# ProPrj_FK407M3-VET6-V1_1-LCD-EB_2024-10-.net
KiCad netlist of a schematic drawn in EasyEDA Pro
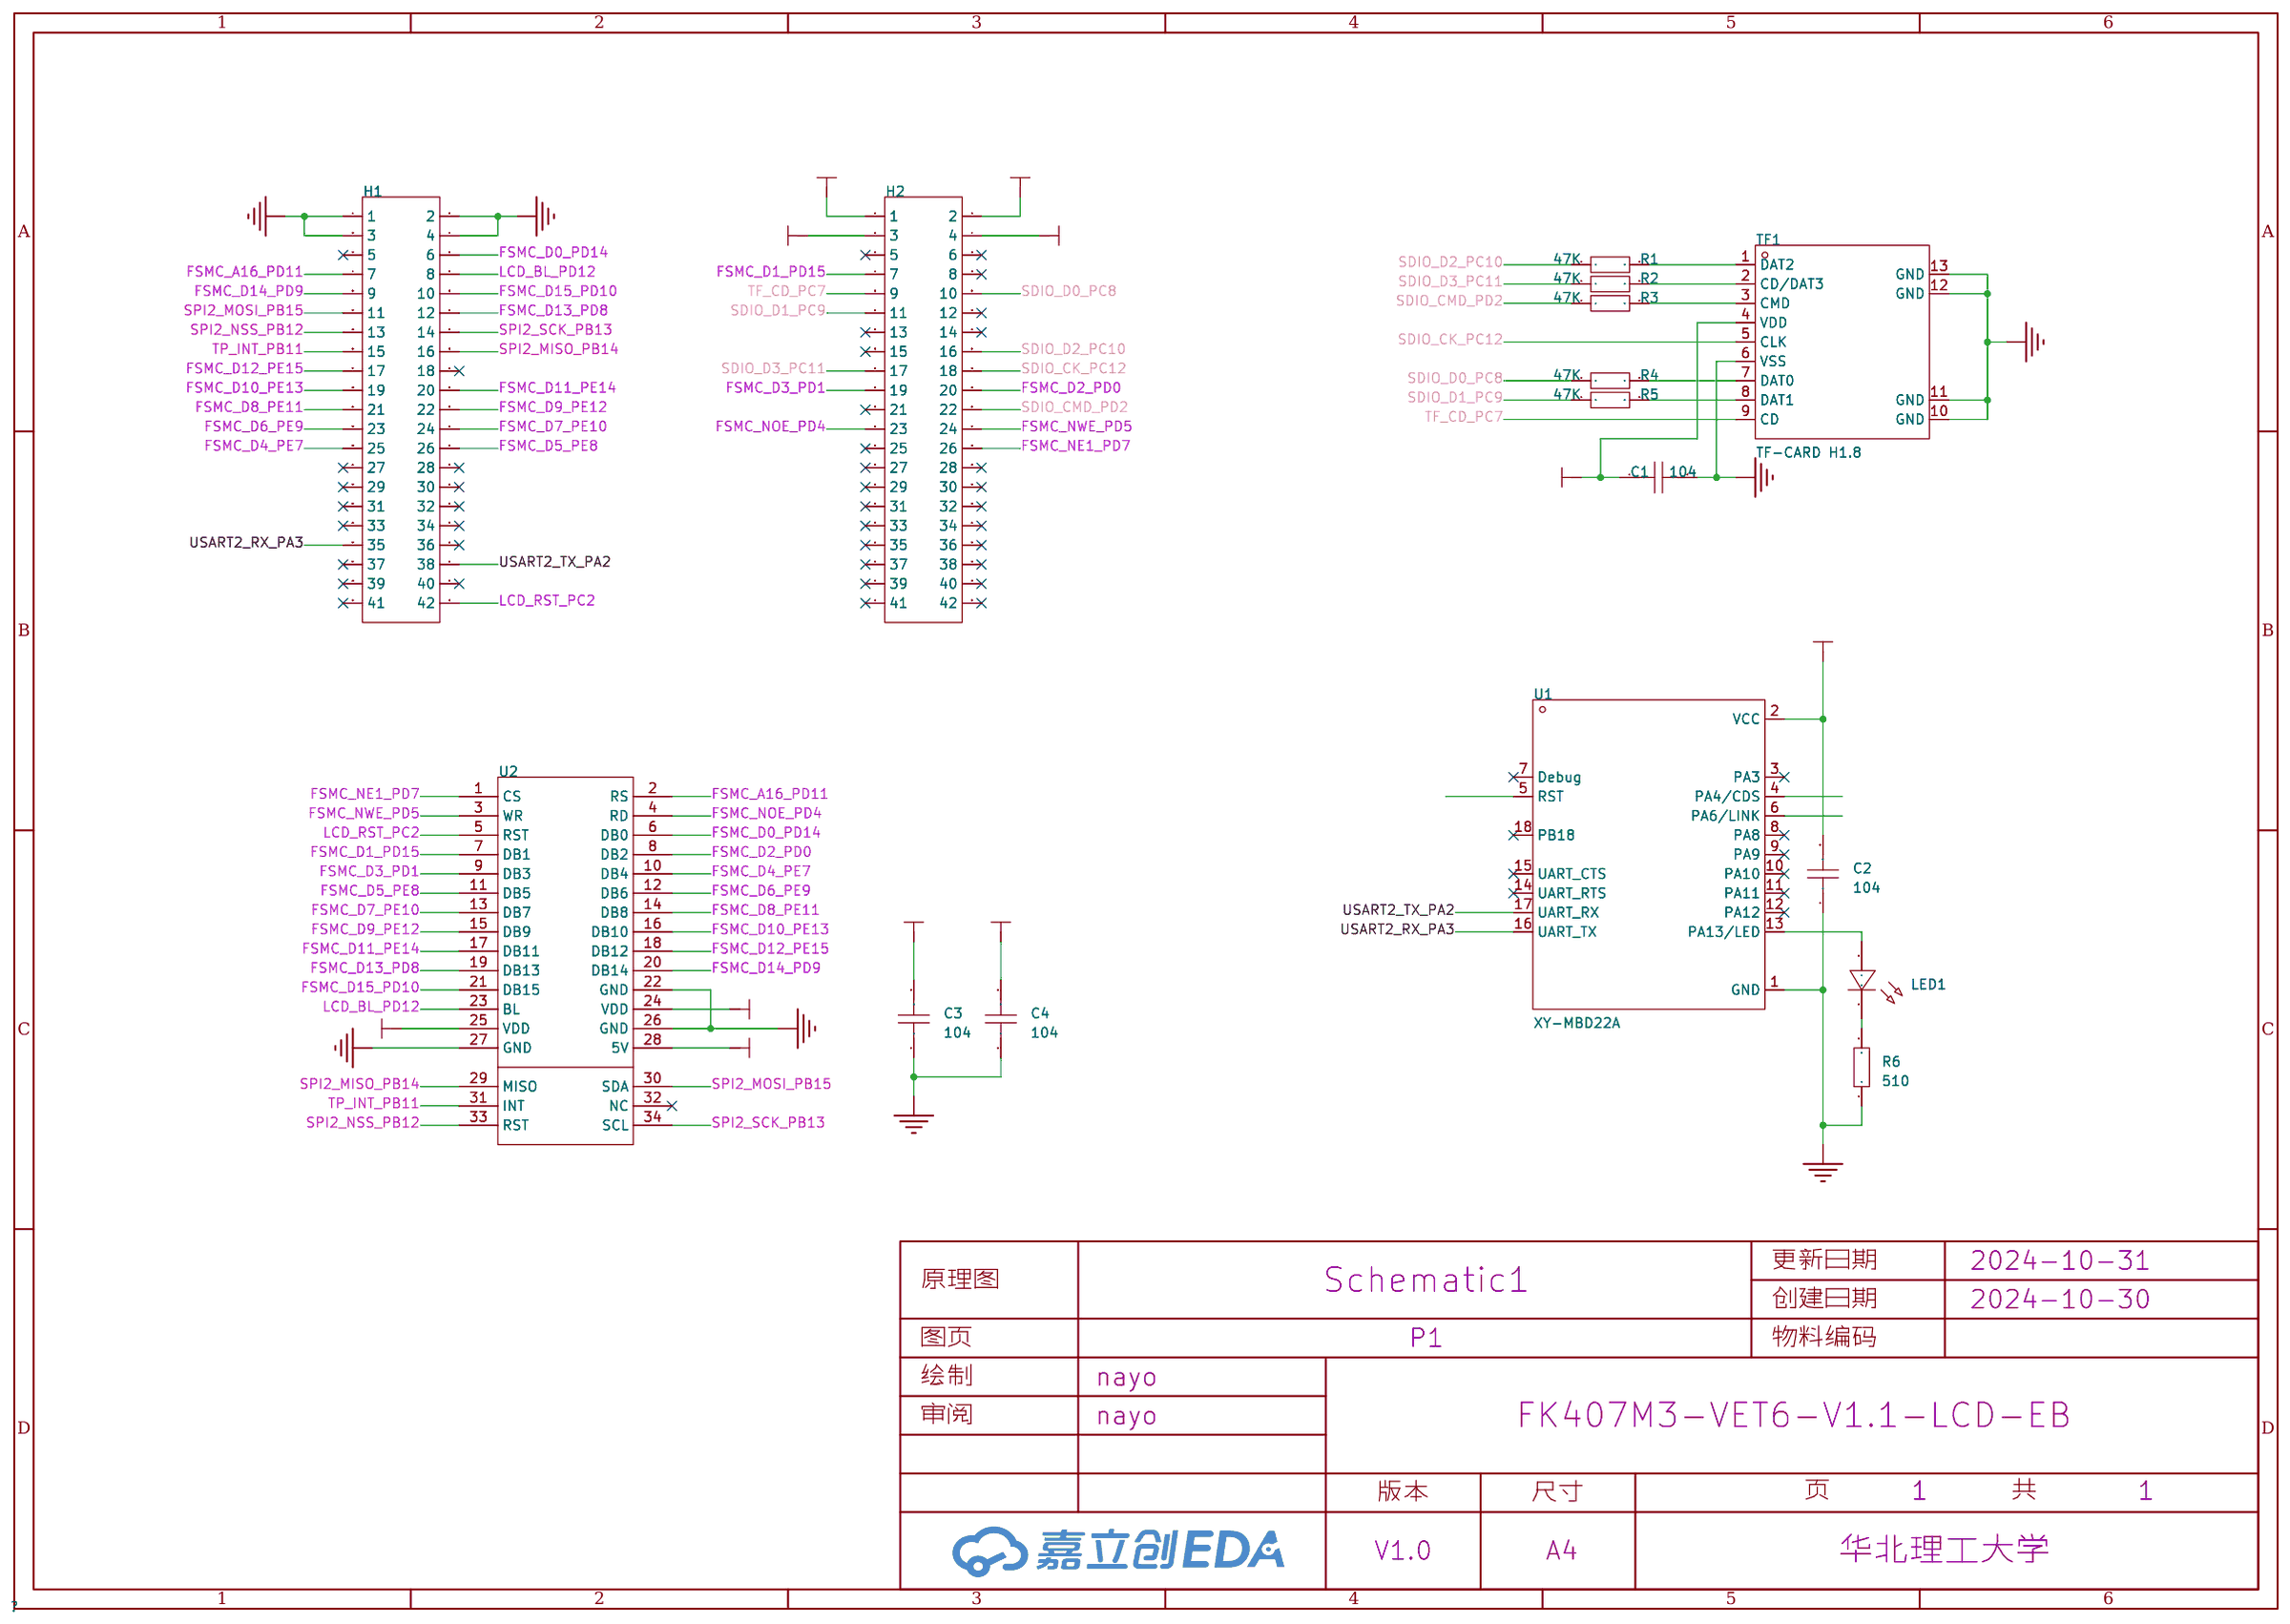
[diagram p0: schematic sheet]

(export (version "E")
  (design (tool "Eeschema 10.0.6"))
  (components
    (comp (ref "C1")
      (value "104")
      (footprint "easyedapro:C0603")
      (libsource (lib "easyedapro") (part "CapAcitance"))
    )
    (comp (ref "C2")
      (value "104")
      (footprint "easyedapro:C0603")
      (libsource (lib "easyedapro") (part "CapAcitance"))
    )
    (comp (ref "C3")
      (value "104")
      (footprint "easyedapro:C0603")
      (libsource (lib "easyedapro") (part "CapAcitance"))
    )
    (comp (ref "C4")
      (value "104")
      (footprint "easyedapro:C0603")
      (libsource (lib "easyedapro") (part "CapAcitance"))
    )
    (comp (ref "H1")
      (value "~")
      (footprint "easyedapro:HDR-F_2.54_2x21P")
      (libsource (lib "easyedapro") (part "HDR-F_2.54_2x21P"))
    )
    (comp (ref "H2")
      (value "~")
      (footprint "easyedapro:HDR-F_2.54_2x21P")
      (libsource (lib "easyedapro") (part "HDR-F_2.54_2x21P"))
    )
    (comp (ref "LED1")
      (value "~")
      (footprint "easyedapro:LED_0603")
      (libsource (lib "easyedapro") (part "LED_B"))
    )
    (comp (ref "R1") (value "47K") (footprint "easyedapro:R0603") (libsource (lib "easyedapro") (part "电阻")))
    (comp (ref "R2") (value "47K") (footprint "easyedapro:R0603") (libsource (lib "easyedapro") (part "电阻")))
    (comp (ref "R3") (value "47K") (footprint "easyedapro:R0603") (libsource (lib "easyedapro") (part "电阻")))
    (comp (ref "R4") (value "47K") (footprint "easyedapro:R0603") (libsource (lib "easyedapro") (part "电阻")))
    (comp (ref "R5") (value "47K") (footprint "easyedapro:R0603") (libsource (lib "easyedapro") (part "电阻")))
    (comp (ref "R6") (value "510") (footprint "easyedapro:R0603") (libsource (lib "easyedapro") (part "电阻")))
    (comp (ref "TF1")
      (value "TF-CARD H1.8")
      (footprint "easyedapro:TF-SMD_TF-CARD-H1.8")
      (description "卡连接方式:自弹式;卡类型:MicroSD卡(TF卡);连接器类型:卡座;本体最大高度:1.8mm;触头材质:铜合金;触头镀层:金;工作温度范围:-40°C~+70°C;")
      (fields (field (name "Manufacturer") "SHOU HAN(首韩)"))
      (libsource (lib "easyedapro") (part "TF-CARD H1.8"))
    )
    (comp (ref "U1")
      (value "XY-MBD22A")
      (footprint "easyedapro:wirelm-smd_xy-mbd22a")
      (libsource (lib "easyedapro") (part "XY-MBD22A"))
    )
    (comp (ref "U2")
      (value "~")
      (footprint "easyedapro:耀元鸿3.5寸TFT液晶显示屏并口串口电阻屏5点电容屏GT911彩屏LCD")
      (libsource (lib "easyedapro") (part "耀元鸿3.5寸TFT液晶显示屏并口串口电阻屏5点电容屏GT911彩屏LCD"))
    )
  )
  (nets
    (net (code "1") (name "/FSMC_A16_PD11") (class "Default")
      (node (ref "H1") (pin "7") (pinfunction "7_7") (pintype "input"))
      (node (ref "U2") (pin "2") (pinfunction "RS_2") (pintype "input"))
    )
    (net (code "2") (name "/FSMC_D0_PD14") (class "Default")
      (node (ref "H1") (pin "6") (pinfunction "6_6") (pintype "input"))
      (node (ref "U2") (pin "6") (pinfunction "DB0_6") (pintype "input"))
    )
    (net (code "3") (name "/FSMC_D1_PD15") (class "Default")
      (node (ref "H2") (pin "7") (pinfunction "7_7") (pintype "input"))
      (node (ref "U2") (pin "7") (pinfunction "DB1_7") (pintype "input"))
    )
    (net (code "4") (name "/FSMC_D2_PD0") (class "Default")
      (node (ref "H2") (pin "20") (pinfunction "20_20") (pintype "input"))
      (node (ref "U2") (pin "8") (pinfunction "DB2_8") (pintype "input"))
    )
    (net (code "5") (name "/FSMC_D3_PD1") (class "Default")
      (node (ref "H2") (pin "19") (pinfunction "19_19") (pintype "input"))
      (node (ref "U2") (pin "9") (pinfunction "DB3_9") (pintype "input"))
    )
    (net (code "6") (name "/FSMC_D4_PE7") (class "Default")
      (node (ref "H1") (pin "25") (pinfunction "25_25") (pintype "input"))
      (node (ref "U2") (pin "10") (pinfunction "DB4_10") (pintype "input"))
    )
    (net (code "7") (name "/FSMC_D5_PE8") (class "Default")
      (node (ref "H1") (pin "26") (pinfunction "26_26") (pintype "input"))
      (node (ref "U2") (pin "11") (pinfunction "DB5_11") (pintype "input"))
    )
    (net (code "8") (name "/FSMC_D6_PE9") (class "Default")
      (node (ref "H1") (pin "23") (pinfunction "23_23") (pintype "input"))
      (node (ref "U2") (pin "12") (pinfunction "DB6_12") (pintype "input"))
    )
    (net (code "9") (name "/FSMC_D7_PE10") (class "Default")
      (node (ref "H1") (pin "24") (pinfunction "24_24") (pintype "input"))
      (node (ref "U2") (pin "13") (pinfunction "DB7_13") (pintype "input"))
    )
    (net (code "10") (name "/FSMC_D8_PE11") (class "Default")
      (node (ref "H1") (pin "21") (pinfunction "21_21") (pintype "input"))
      (node (ref "U2") (pin "14") (pinfunction "DB8_14") (pintype "input"))
    )
    (net (code "11") (name "/FSMC_D9_PE12") (class "Default")
      (node (ref "H1") (pin "22") (pinfunction "22_22") (pintype "input"))
      (node (ref "U2") (pin "15") (pinfunction "DB9_15") (pintype "input"))
    )
    (net (code "12") (name "/FSMC_D10_PE13") (class "Default")
      (node (ref "H1") (pin "19") (pinfunction "19_19") (pintype "input"))
      (node (ref "U2") (pin "16") (pinfunction "DB10_16") (pintype "input"))
    )
    (net (code "13") (name "/FSMC_D11_PE14") (class "Default")
      (node (ref "H1") (pin "20") (pinfunction "20_20") (pintype "input"))
      (node (ref "U2") (pin "17") (pinfunction "DB11_17") (pintype "input"))
    )
    (net (code "14") (name "/FSMC_D12_PE15") (class "Default")
      (node (ref "H1") (pin "17") (pinfunction "17_17") (pintype "input"))
      (node (ref "U2") (pin "18") (pinfunction "DB12_18") (pintype "input"))
    )
    (net (code "15") (name "/FSMC_D13_PD8") (class "Default")
      (node (ref "H1") (pin "12") (pinfunction "12_12") (pintype "input"))
      (node (ref "U2") (pin "19") (pinfunction "DB13_19") (pintype "input"))
    )
    (net (code "16") (name "/FSMC_D14_PD9") (class "Default")
      (node (ref "H1") (pin "9") (pinfunction "9_9") (pintype "input"))
      (node (ref "U2") (pin "20") (pinfunction "DB14_20") (pintype "input"))
    )
    (net (code "17") (name "/FSMC_D15_PD10") (class "Default")
      (node (ref "H1") (pin "10") (pinfunction "10_10") (pintype "input"))
      (node (ref "U2") (pin "21") (pinfunction "DB15_21") (pintype "input"))
    )
    (net (code "18") (name "/FSMC_NE1_PD7") (class "Default")
      (node (ref "H2") (pin "26") (pinfunction "26_26") (pintype "input"))
      (node (ref "U2") (pin "1") (pinfunction "CS_1") (pintype "input"))
    )
    (net (code "19") (name "/FSMC_NOE_PD4") (class "Default")
      (node (ref "H2") (pin "23") (pinfunction "23_23") (pintype "input"))
      (node (ref "U2") (pin "4") (pinfunction "RD_4") (pintype "input"))
    )
    (net (code "20") (name "/FSMC_NWE_PD5") (class "Default")
      (node (ref "H2") (pin "24") (pinfunction "24_24") (pintype "input"))
      (node (ref "U2") (pin "3") (pinfunction "WR_3") (pintype "input"))
    )
    (net (code "21") (name "/LCD_BL_PD12") (class "Default")
      (node (ref "H1") (pin "8") (pinfunction "8_8") (pintype "input"))
      (node (ref "U2") (pin "23") (pinfunction "BL_23") (pintype "input"))
    )
    (net (code "22") (name "/LCD_RST_PC2") (class "Default")
      (node (ref "H1") (pin "42") (pinfunction "42_42") (pintype "input"))
      (node (ref "U2") (pin "5") (pinfunction "RST_5") (pintype "input"))
    )
    (net (code "23") (name "/SDIO_CK_PC12") (class "Default")
      (node (ref "H2") (pin "18") (pinfunction "18_18") (pintype "input"))
      (node (ref "TF1") (pin "5") (pinfunction "CLK_5") (pintype "unspecified"))
    )
    (net (code "24") (name "/SDIO_CMD_PD2") (class "Default")
      (node (ref "H2") (pin "22") (pinfunction "22_22") (pintype "input"))
      (node (ref "R3") (pin "1") (pinfunction "1_1") (pintype "input"))
    )
    (net (code "25") (name "/SDIO_D0_PC8") (class "Default")
      (node (ref "H2") (pin "10") (pinfunction "10_10") (pintype "input"))
      (node (ref "R4") (pin "1") (pinfunction "1_1") (pintype "input"))
    )
    (net (code "26") (name "/SDIO_D1_PC9") (class "Default")
      (node (ref "H2") (pin "11") (pinfunction "11_11") (pintype "input"))
      (node (ref "R5") (pin "1") (pinfunction "1_1") (pintype "input"))
    )
    (net (code "27") (name "/SDIO_D2_PC10") (class "Default")
      (node (ref "H2") (pin "16") (pinfunction "16_16") (pintype "input"))
      (node (ref "R1") (pin "1") (pinfunction "1_1") (pintype "input"))
    )
    (net (code "28") (name "/SDIO_D3_PC11") (class "Default")
      (node (ref "H2") (pin "17") (pinfunction "17_17") (pintype "input"))
      (node (ref "R2") (pin "1") (pinfunction "1_1") (pintype "input"))
    )
    (net (code "29") (name "/SPI2_MISO_PB14") (class "Default")
      (node (ref "H1") (pin "16") (pinfunction "16_16") (pintype "input"))
      (node (ref "U2") (pin "29") (pinfunction "MISO_29") (pintype "input"))
    )
    (net (code "30") (name "/SPI2_MOSI_PB15") (class "Default")
      (node (ref "H1") (pin "11") (pinfunction "11_11") (pintype "input"))
      (node (ref "U2") (pin "30") (pinfunction "SDA_30") (pintype "input"))
    )
    (net (code "31") (name "/SPI2_NSS_PB12") (class "Default")
      (node (ref "H1") (pin "13") (pinfunction "13_13") (pintype "input"))
      (node (ref "U2") (pin "33") (pinfunction "RST_33") (pintype "input"))
    )
    (net (code "32") (name "/SPI2_SCK_PB13") (class "Default")
      (node (ref "H1") (pin "14") (pinfunction "14_14") (pintype "input"))
      (node (ref "U2") (pin "34") (pinfunction "SCL_34") (pintype "input"))
    )
    (net (code "33") (name "/TF_CD_PC7") (class "Default")
      (node (ref "H2") (pin "9") (pinfunction "9_9") (pintype "input"))
      (node (ref "TF1") (pin "9") (pinfunction "CD_9") (pintype "unspecified"))
    )
    (net (code "34") (name "/TP_INT_PB11") (class "Default")
      (node (ref "H1") (pin "15") (pinfunction "15_15") (pintype "input"))
      (node (ref "U2") (pin "31") (pinfunction "INT_31") (pintype "input"))
    )
    (net (code "35") (name "/USART2_RX_PA3") (class "Default")
      (node (ref "H1") (pin "35") (pinfunction "35_35") (pintype "input"))
      (node (ref "U1") (pin "16") (pinfunction "UART_TX_16") (pintype "unspecified"))
    )
    (net (code "36") (name "/USART2_TX_PA2") (class "Default")
      (node (ref "H1") (pin "38") (pinfunction "38_38") (pintype "input"))
      (node (ref "U1") (pin "17") (pinfunction "UART_RX_17") (pintype "unspecified"))
    )
    (net (code "37") (name "3V3") (class "Default")
      (node (ref "C1") (pin "1") (pinfunction "1_1") (pintype "input"))
      (node (ref "C2") (pin "2") (pinfunction "2_2") (pintype "input"))
      (node (ref "C4") (pin "2") (pinfunction "2_2") (pintype "input"))
      (node (ref "H2") (pin "3") (pinfunction "3_3") (pintype "input"))
      (node (ref "H2") (pin "4") (pinfunction "4_4") (pintype "input"))
      (node (ref "TF1") (pin "4") (pinfunction "VDD_4") (pintype "unspecified"))
      (node (ref "U1") (pin "2") (pinfunction "VCC_2") (pintype "unspecified"))
      (node (ref "U2") (pin "24") (pinfunction "VDD_24") (pintype "input"))
      (node (ref "U2") (pin "25") (pinfunction "VDD_25") (pintype "input"))
    )
    (net (code "38") (name "5V") (class "Default")
      (node (ref "C3") (pin "2") (pinfunction "2_2") (pintype "input"))
      (node (ref "H2") (pin "1") (pinfunction "1_1") (pintype "input"))
      (node (ref "H2") (pin "2") (pinfunction "2_2") (pintype "input"))
      (node (ref "U2") (pin "28") (pinfunction "5V_28") (pintype "input"))
    )
    (net (code "39") (name "GND") (class "Default")
      (node (ref "C1") (pin "2") (pinfunction "2_2") (pintype "input"))
      (node (ref "C2") (pin "1") (pinfunction "1_1") (pintype "input"))
      (node (ref "C3") (pin "1") (pinfunction "1_1") (pintype "input"))
      (node (ref "C4") (pin "1") (pinfunction "1_1") (pintype "input"))
      (node (ref "H1") (pin "1") (pinfunction "1_1") (pintype "input"))
      (node (ref "H1") (pin "2") (pinfunction "2_2") (pintype "input"))
      (node (ref "H1") (pin "3") (pinfunction "3_3") (pintype "input"))
      (node (ref "H1") (pin "4") (pinfunction "4_4") (pintype "input"))
      (node (ref "R6") (pin "1") (pinfunction "1_1") (pintype "input"))
      (node (ref "TF1") (pin "10") (pinfunction "GND_10") (pintype "unspecified"))
      (node (ref "TF1") (pin "11") (pinfunction "GND_11") (pintype "unspecified"))
      (node (ref "TF1") (pin "12") (pinfunction "GND_12") (pintype "unspecified"))
      (node (ref "TF1") (pin "13") (pinfunction "GND_13") (pintype "unspecified"))
      (node (ref "TF1") (pin "6") (pinfunction "VSS_6") (pintype "unspecified"))
      (node (ref "U1") (pin "1") (pinfunction "GND_1") (pintype "unspecified"))
      (node (ref "U2") (pin "22") (pinfunction "GND_22") (pintype "input"))
      (node (ref "U2") (pin "26") (pinfunction "GND_26") (pintype "input"))
      (node (ref "U2") (pin "27") (pinfunction "GND_27") (pintype "input"))
    )
    (net (code "40") (name "Net-(LED1-A)") (class "Default")
      (node (ref "LED1") (pin "2") (pinfunction "A_2") (pintype "input"))
      (node (ref "U1") (pin "13") (pinfunction "PA13/LED_13") (pintype "unspecified"))
    )
    (net (code "41") (name "Net-(LED1-C)") (class "Default")
      (node (ref "LED1") (pin "1") (pinfunction "C_1") (pintype "input"))
      (node (ref "R6") (pin "2") (pinfunction "2_2") (pintype "input"))
    )
    (net (code "42") (name "Net-(TF1-CD{slash}DAT3)") (class "Default")
      (node (ref "R2") (pin "2") (pinfunction "2_2") (pintype "input"))
      (node (ref "TF1") (pin "2") (pinfunction "CD/DAT3_2") (pintype "unspecified"))
    )
    (net (code "43") (name "Net-(TF1-CMD)") (class "Default")
      (node (ref "R3") (pin "2") (pinfunction "2_2") (pintype "input"))
      (node (ref "TF1") (pin "3") (pinfunction "CMD_3") (pintype "unspecified"))
    )
    (net (code "44") (name "Net-(TF1-DAT0)") (class "Default")
      (node (ref "R4") (pin "2") (pinfunction "2_2") (pintype "input"))
      (node (ref "TF1") (pin "7") (pinfunction "DAT0_7") (pintype "unspecified"))
    )
    (net (code "45") (name "Net-(TF1-DAT1)") (class "Default")
      (node (ref "R5") (pin "2") (pinfunction "2_2") (pintype "input"))
      (node (ref "TF1") (pin "8") (pinfunction "DAT1_8") (pintype "unspecified"))
    )
    (net (code "46") (name "Net-(TF1-DAT2)") (class "Default")
      (node (ref "R1") (pin "2") (pinfunction "2_2") (pintype "input"))
      (node (ref "TF1") (pin "1") (pinfunction "DAT2_1") (pintype "unspecified"))
    )
    (net (code "47") (name "unconnected-(H1-Pad5)") (class "Default")
      (node (ref "H1") (pin "5") (pinfunction "5_5") (pintype "input+no_connect"))
    )
    (net (code "48") (name "unconnected-(H1-Pad18)") (class "Default")
      (node (ref "H1") (pin "18") (pinfunction "18_18") (pintype "input+no_connect"))
    )
    (net (code "49") (name "unconnected-(H1-Pad27)") (class "Default")
      (node (ref "H1") (pin "27") (pinfunction "27_27") (pintype "input+no_connect"))
    )
    (net (code "50") (name "unconnected-(H1-Pad28)") (class "Default")
      (node (ref "H1") (pin "28") (pinfunction "28_28") (pintype "input+no_connect"))
    )
    (net (code "51") (name "unconnected-(H1-Pad29)") (class "Default")
      (node (ref "H1") (pin "29") (pinfunction "29_29") (pintype "input+no_connect"))
    )
    (net (code "52") (name "unconnected-(H1-Pad30)") (class "Default")
      (node (ref "H1") (pin "30") (pinfunction "30_30") (pintype "input+no_connect"))
    )
    (net (code "53") (name "unconnected-(H1-Pad31)") (class "Default")
      (node (ref "H1") (pin "31") (pinfunction "31_31") (pintype "input+no_connect"))
    )
    (net (code "54") (name "unconnected-(H1-Pad32)") (class "Default")
      (node (ref "H1") (pin "32") (pinfunction "32_32") (pintype "input+no_connect"))
    )
    (net (code "55") (name "unconnected-(H1-Pad33)") (class "Default")
      (node (ref "H1") (pin "33") (pinfunction "33_33") (pintype "input+no_connect"))
    )
    (net (code "56") (name "unconnected-(H1-Pad34)") (class "Default")
      (node (ref "H1") (pin "34") (pinfunction "34_34") (pintype "input+no_connect"))
    )
    (net (code "57") (name "unconnected-(H1-Pad36)") (class "Default")
      (node (ref "H1") (pin "36") (pinfunction "36_36") (pintype "input+no_connect"))
    )
    (net (code "58") (name "unconnected-(H1-Pad37)") (class "Default")
      (node (ref "H1") (pin "37") (pinfunction "37_37") (pintype "input+no_connect"))
    )
    (net (code "59") (name "unconnected-(H1-Pad39)") (class "Default")
      (node (ref "H1") (pin "39") (pinfunction "39_39") (pintype "input+no_connect"))
    )
    (net (code "60") (name "unconnected-(H1-Pad40)") (class "Default")
      (node (ref "H1") (pin "40") (pinfunction "40_40") (pintype "input+no_connect"))
    )
    (net (code "61") (name "unconnected-(H1-Pad41)") (class "Default")
      (node (ref "H1") (pin "41") (pinfunction "41_41") (pintype "input+no_connect"))
    )
    (net (code "62") (name "unconnected-(H2-Pad5)") (class "Default")
      (node (ref "H2") (pin "5") (pinfunction "5_5") (pintype "input+no_connect"))
    )
    (net (code "63") (name "unconnected-(H2-Pad6)") (class "Default")
      (node (ref "H2") (pin "6") (pinfunction "6_6") (pintype "input+no_connect"))
    )
    (net (code "64") (name "unconnected-(H2-Pad8)") (class "Default")
      (node (ref "H2") (pin "8") (pinfunction "8_8") (pintype "input+no_connect"))
    )
    (net (code "65") (name "unconnected-(H2-Pad12)") (class "Default")
      (node (ref "H2") (pin "12") (pinfunction "12_12") (pintype "input+no_connect"))
    )
    (net (code "66") (name "unconnected-(H2-Pad13)") (class "Default")
      (node (ref "H2") (pin "13") (pinfunction "13_13") (pintype "input+no_connect"))
    )
    (net (code "67") (name "unconnected-(H2-Pad14)") (class "Default")
      (node (ref "H2") (pin "14") (pinfunction "14_14") (pintype "input+no_connect"))
    )
    (net (code "68") (name "unconnected-(H2-Pad15)") (class "Default")
      (node (ref "H2") (pin "15") (pinfunction "15_15") (pintype "input+no_connect"))
    )
    (net (code "69") (name "unconnected-(H2-Pad21)") (class "Default")
      (node (ref "H2") (pin "21") (pinfunction "21_21") (pintype "input+no_connect"))
    )
    (net (code "70") (name "unconnected-(H2-Pad25)") (class "Default")
      (node (ref "H2") (pin "25") (pinfunction "25_25") (pintype "input+no_connect"))
    )
    (net (code "71") (name "unconnected-(H2-Pad27)") (class "Default")
      (node (ref "H2") (pin "27") (pinfunction "27_27") (pintype "input+no_connect"))
    )
    (net (code "72") (name "unconnected-(H2-Pad28)") (class "Default")
      (node (ref "H2") (pin "28") (pinfunction "28_28") (pintype "input+no_connect"))
    )
    (net (code "73") (name "unconnected-(H2-Pad29)") (class "Default")
      (node (ref "H2") (pin "29") (pinfunction "29_29") (pintype "input+no_connect"))
    )
    (net (code "74") (name "unconnected-(H2-Pad30)") (class "Default")
      (node (ref "H2") (pin "30") (pinfunction "30_30") (pintype "input+no_connect"))
    )
    (net (code "75") (name "unconnected-(H2-Pad31)") (class "Default")
      (node (ref "H2") (pin "31") (pinfunction "31_31") (pintype "input+no_connect"))
    )
    (net (code "76") (name "unconnected-(H2-Pad32)") (class "Default")
      (node (ref "H2") (pin "32") (pinfunction "32_32") (pintype "input+no_connect"))
    )
    (net (code "77") (name "unconnected-(H2-Pad33)") (class "Default")
      (node (ref "H2") (pin "33") (pinfunction "33_33") (pintype "input+no_connect"))
    )
    (net (code "78") (name "unconnected-(H2-Pad34)") (class "Default")
      (node (ref "H2") (pin "34") (pinfunction "34_34") (pintype "input+no_connect"))
    )
    (net (code "79") (name "unconnected-(H2-Pad35)") (class "Default")
      (node (ref "H2") (pin "35") (pinfunction "35_35") (pintype "input+no_connect"))
    )
    (net (code "80") (name "unconnected-(H2-Pad36)") (class "Default")
      (node (ref "H2") (pin "36") (pinfunction "36_36") (pintype "input+no_connect"))
    )
    (net (code "81") (name "unconnected-(H2-Pad37)") (class "Default")
      (node (ref "H2") (pin "37") (pinfunction "37_37") (pintype "input+no_connect"))
    )
    (net (code "82") (name "unconnected-(H2-Pad38)") (class "Default")
      (node (ref "H2") (pin "38") (pinfunction "38_38") (pintype "input+no_connect"))
    )
    (net (code "83") (name "unconnected-(H2-Pad39)") (class "Default")
      (node (ref "H2") (pin "39") (pinfunction "39_39") (pintype "input+no_connect"))
    )
    (net (code "84") (name "unconnected-(H2-Pad40)") (class "Default")
      (node (ref "H2") (pin "40") (pinfunction "40_40") (pintype "input+no_connect"))
    )
    (net (code "85") (name "unconnected-(H2-Pad41)") (class "Default")
      (node (ref "H2") (pin "41") (pinfunction "41_41") (pintype "input+no_connect"))
    )
    (net (code "86") (name "unconnected-(H2-Pad42)") (class "Default")
      (node (ref "H2") (pin "42") (pinfunction "42_42") (pintype "input+no_connect"))
    )
    (net (code "87") (name "unconnected-(U1-Debug-Pad7)") (class "Default")
      (node (ref "U1") (pin "7") (pinfunction "Debug_7") (pintype "unspecified+no_connect"))
    )
    (net (code "88") (name "unconnected-(U1-PA3-Pad3)") (class "Default")
      (node (ref "U1") (pin "3") (pinfunction "PA3_3") (pintype "unspecified+no_connect"))
    )
    (net (code "89") (name "unconnected-(U1-PA4{slash}CDS-Pad4)") (class "Default")
      (node (ref "U1") (pin "4") (pinfunction "PA4/CDS_4") (pintype "unspecified"))
    )
    (net (code "90") (name "unconnected-(U1-PA6{slash}LINK-Pad6)") (class "Default")
      (node (ref "U1") (pin "6") (pinfunction "PA6/LINK_6") (pintype "unspecified"))
    )
    (net (code "91") (name "unconnected-(U1-PA8-Pad8)") (class "Default")
      (node (ref "U1") (pin "8") (pinfunction "PA8_8") (pintype "unspecified+no_connect"))
    )
    (net (code "92") (name "unconnected-(U1-PA9-Pad9)") (class "Default")
      (node (ref "U1") (pin "9") (pinfunction "PA9_9") (pintype "unspecified+no_connect"))
    )
    (net (code "93") (name "unconnected-(U1-PA10-Pad10)") (class "Default")
      (node (ref "U1") (pin "10") (pinfunction "PA10_10") (pintype "unspecified+no_connect"))
    )
    (net (code "94") (name "unconnected-(U1-PA11-Pad11)") (class "Default")
      (node (ref "U1") (pin "11") (pinfunction "PA11_11") (pintype "unspecified+no_connect"))
    )
    (net (code "95") (name "unconnected-(U1-PA12-Pad12)") (class "Default")
      (node (ref "U1") (pin "12") (pinfunction "PA12_12") (pintype "unspecified+no_connect"))
    )
    (net (code "96") (name "unconnected-(U1-PB18-Pad18)") (class "Default")
      (node (ref "U1") (pin "18") (pinfunction "PB18_18") (pintype "unspecified+no_connect"))
    )
    (net (code "97") (name "unconnected-(U1-RST-Pad5)") (class "Default")
      (node (ref "U1") (pin "5") (pinfunction "RST_5") (pintype "unspecified"))
    )
    (net (code "98") (name "unconnected-(U1-UART_CTS-Pad15)") (class "Default")
      (node (ref "U1") (pin "15") (pinfunction "UART_CTS_15") (pintype "unspecified+no_connect"))
    )
    (net (code "99") (name "unconnected-(U1-UART_RTS-Pad14)") (class "Default")
      (node (ref "U1") (pin "14") (pinfunction "UART_RTS_14") (pintype "unspecified+no_connect"))
    )
    (net (code "100") (name "unconnected-(U2-NC-Pad32)") (class "Default")
      (node (ref "U2") (pin "32") (pinfunction "NC_32") (pintype "input+no_connect"))
    )
  )
)
